# ButterflyFC.net
KiCad netlist of a schematic drawn in EAGLE
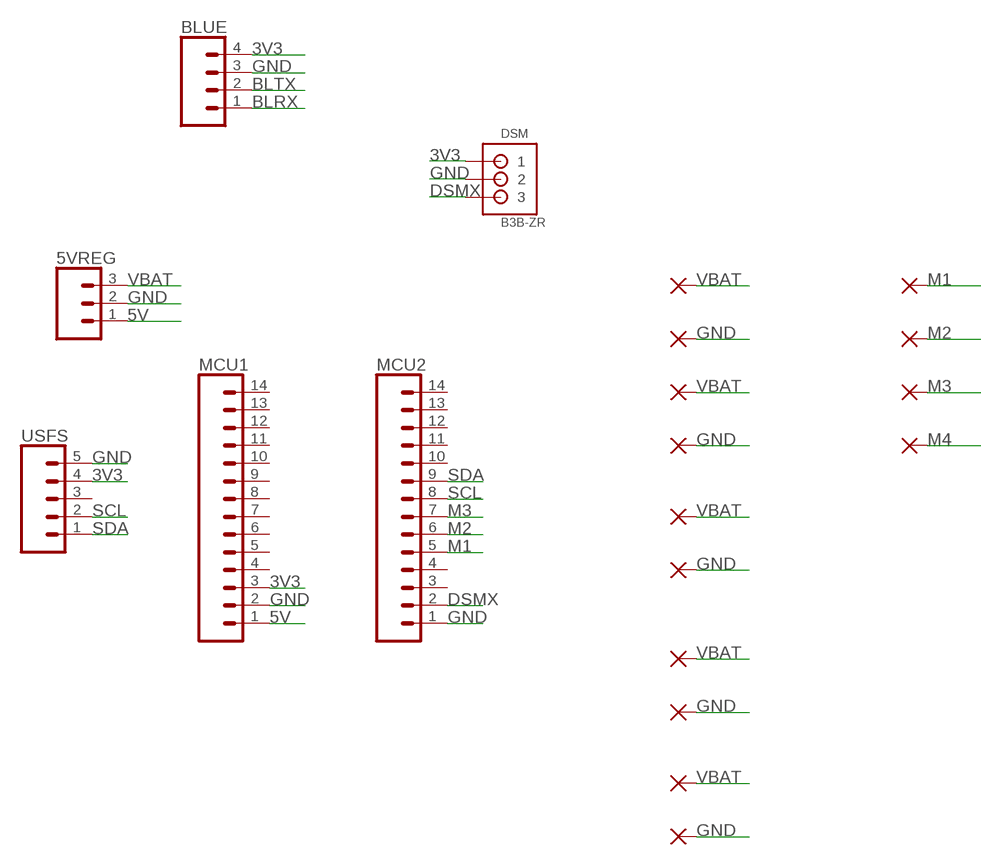
[diagram p0: schematic, sheet 1]

(export (version "E")
  (design (tool "Eeschema 10.0.6"))
  (components
    (comp (ref "5VREG")
      (value "CONN_031X03_NO_SILK")
      (footprint "eagle-import:1X03_NO_SILK")
      (libsource (lib "eagle-import") (part "CONN_031X03_NO_SILK"))
    )
    (comp (ref "BLUE")
      (value "CONN_041X04_NO_SILK")
      (footprint "eagle-import:1X04_NO_SILK")
      (libsource (lib "eagle-import") (part "CONN_041X04_NO_SILK"))
    )
    (comp (ref "DSM")
      (value "B3B-ZR")
      (footprint "eagle-import:B3B-ZR")
      (libsource (lib "eagle-import") (part "B3B-ZR"))
    )
    (comp (ref "MCU1")
      (value "CONN_14NO_SILK")
      (footprint "eagle-import:1X14_NO_SILK")
      (libsource (lib "eagle-import") (part "CONN_14NO_SILK"))
    )
    (comp (ref "MCU2")
      (value "CONN_14NO_SILK")
      (footprint "eagle-import:1X14_NO_SILK")
      (libsource (lib "eagle-import") (part "CONN_14NO_SILK"))
    )
    (comp (ref "PAD1")
      (value "WIREPADSMD5-2,5")
      (footprint "eagle-import:5-2,5")
      (libsource (lib "eagle-import") (part "WIREPADSMD5-2,5"))
    )
    (comp (ref "PAD2")
      (value "WIREPADSMD5-2,5")
      (footprint "eagle-import:5-2,5")
      (libsource (lib "eagle-import") (part "WIREPADSMD5-2,5"))
    )
    (comp (ref "PAD3")
      (value "WIREPADSMD5-2,5")
      (footprint "eagle-import:5-2,5")
      (libsource (lib "eagle-import") (part "WIREPADSMD5-2,5"))
    )
    (comp (ref "PAD4")
      (value "WIREPADSMD5-2,5")
      (footprint "eagle-import:5-2,5")
      (libsource (lib "eagle-import") (part "WIREPADSMD5-2,5"))
    )
    (comp (ref "PAD5")
      (value "WIREPADSMD5-2,5")
      (footprint "eagle-import:5-2,5")
      (libsource (lib "eagle-import") (part "WIREPADSMD5-2,5"))
    )
    (comp (ref "PAD6")
      (value "WIREPADSMD5-2,5")
      (footprint "eagle-import:5-2,5")
      (libsource (lib "eagle-import") (part "WIREPADSMD5-2,5"))
    )
    (comp (ref "PAD7")
      (value "WIREPADSMD5-2,5")
      (footprint "eagle-import:5-2,5")
      (libsource (lib "eagle-import") (part "WIREPADSMD5-2,5"))
    )
    (comp (ref "PAD8")
      (value "WIREPADSMD5-2,5")
      (footprint "eagle-import:5-2,5")
      (libsource (lib "eagle-import") (part "WIREPADSMD5-2,5"))
    )
    (comp (ref "PAD9")
      (value "WIREPADSMD5-2,5")
      (footprint "eagle-import:5-2,5")
      (libsource (lib "eagle-import") (part "WIREPADSMD5-2,5"))
    )
    (comp (ref "PAD10")
      (value "WIREPADSMD5-2,5")
      (footprint "eagle-import:5-2,5")
      (libsource (lib "eagle-import") (part "WIREPADSMD5-2,5"))
    )
    (comp (ref "PAD11")
      (value "WIREPADSMD5-2,5")
      (footprint "eagle-import:5-2,5")
      (libsource (lib "eagle-import") (part "WIREPADSMD5-2,5"))
    )
    (comp (ref "PAD12")
      (value "WIREPADSMD5-2,5")
      (footprint "eagle-import:5-2,5")
      (libsource (lib "eagle-import") (part "WIREPADSMD5-2,5"))
    )
    (comp (ref "PAD13")
      (value "WIREPADSMD5-2,5")
      (footprint "eagle-import:5-2,5")
      (libsource (lib "eagle-import") (part "WIREPADSMD5-2,5"))
    )
    (comp (ref "PAD14")
      (value "WIREPADSMD5-2,5")
      (footprint "eagle-import:5-2,5")
      (libsource (lib "eagle-import") (part "WIREPADSMD5-2,5"))
    )
    (comp (ref "USFS")
      (value "CONN_05NO_SILK")
      (footprint "eagle-import:1X05_NO_SILK")
      (libsource (lib "eagle-import") (part "CONN_05NO_SILK"))
    )
  )
  (nets
    (net (code "1") (name "/3V3") (class "Default")
      (node (ref "BLUE") (pin "4") (pinfunction "4_4") (pintype "passive"))
      (node (ref "DSM") (pin "1") (pinfunction "1_1") (pintype "bidirectional"))
      (node (ref "MCU1") (pin "3") (pinfunction "3_3") (pintype "passive"))
      (node (ref "USFS") (pin "4") (pinfunction "4_4") (pintype "passive"))
    )
    (net (code "2") (name "/5V") (class "Default")
      (node (ref "5VREG") (pin "1") (pinfunction "1_1") (pintype "passive"))
      (node (ref "MCU1") (pin "1") (pinfunction "1_1") (pintype "passive"))
    )
    (net (code "3") (name "/BLRX") (class "Default")
      (node (ref "BLUE") (pin "1") (pinfunction "1_1") (pintype "passive"))
    )
    (net (code "4") (name "/BLTX") (class "Default")
      (node (ref "BLUE") (pin "2") (pinfunction "2_2") (pintype "passive"))
    )
    (net (code "5") (name "/DSMX") (class "Default")
      (node (ref "DSM") (pin "3") (pinfunction "3_3") (pintype "bidirectional"))
      (node (ref "MCU2") (pin "2") (pinfunction "2_2") (pintype "passive"))
    )
    (net (code "6") (name "/GND") (class "Default")
      (node (ref "5VREG") (pin "2") (pinfunction "2_2") (pintype "passive"))
      (node (ref "BLUE") (pin "3") (pinfunction "3_3") (pintype "passive"))
      (node (ref "DSM") (pin "2") (pinfunction "2_2") (pintype "bidirectional"))
      (node (ref "MCU1") (pin "2") (pinfunction "2_2") (pintype "passive"))
      (node (ref "MCU2") (pin "1") (pinfunction "1_1") (pintype "passive"))
      (node (ref "PAD10") (pin "1") (pinfunction "P_1") (pintype "passive"))
      (node (ref "PAD2") (pin "1") (pinfunction "P_1") (pintype "passive"))
      (node (ref "PAD4") (pin "1") (pinfunction "P_1") (pintype "passive"))
      (node (ref "PAD6") (pin "1") (pinfunction "P_1") (pintype "passive"))
      (node (ref "PAD8") (pin "1") (pinfunction "P_1") (pintype "passive"))
      (node (ref "USFS") (pin "5") (pinfunction "5_5") (pintype "passive"))
    )
    (net (code "7") (name "/M1") (class "Default")
      (node (ref "MCU2") (pin "5") (pinfunction "5_5") (pintype "passive"))
      (node (ref "PAD13") (pin "1") (pinfunction "P_1") (pintype "passive"))
    )
    (net (code "8") (name "/M2") (class "Default")
      (node (ref "MCU2") (pin "6") (pinfunction "6_6") (pintype "passive"))
      (node (ref "PAD14") (pin "1") (pinfunction "P_1") (pintype "passive"))
    )
    (net (code "9") (name "/M3") (class "Default")
      (node (ref "MCU2") (pin "7") (pinfunction "7_7") (pintype "passive"))
      (node (ref "PAD11") (pin "1") (pinfunction "P_1") (pintype "passive"))
    )
    (net (code "10") (name "/M4") (class "Default")
      (node (ref "PAD12") (pin "1") (pinfunction "P_1") (pintype "passive"))
    )
    (net (code "11") (name "/SCL") (class "Default")
      (node (ref "MCU2") (pin "8") (pinfunction "8_8") (pintype "passive"))
      (node (ref "USFS") (pin "2") (pinfunction "2_2") (pintype "passive"))
    )
    (net (code "12") (name "/SDA") (class "Default")
      (node (ref "MCU2") (pin "9") (pinfunction "9_9") (pintype "passive"))
      (node (ref "USFS") (pin "1") (pinfunction "1_1") (pintype "passive"))
    )
    (net (code "13") (name "/VBAT") (class "Default")
      (node (ref "5VREG") (pin "3") (pinfunction "3_3") (pintype "passive"))
      (node (ref "PAD1") (pin "1") (pinfunction "P_1") (pintype "passive"))
      (node (ref "PAD3") (pin "1") (pinfunction "P_1") (pintype "passive"))
      (node (ref "PAD5") (pin "1") (pinfunction "P_1") (pintype "passive"))
      (node (ref "PAD7") (pin "1") (pinfunction "P_1") (pintype "passive"))
      (node (ref "PAD9") (pin "1") (pinfunction "P_1") (pintype "passive"))
    )
    (net (code "14") (name "unconnected-(MCU1-Pad4)") (class "Default")
      (node (ref "MCU1") (pin "4") (pinfunction "4_4") (pintype "passive"))
    )
    (net (code "15") (name "unconnected-(MCU1-Pad5)") (class "Default")
      (node (ref "MCU1") (pin "5") (pinfunction "5_5") (pintype "passive"))
    )
    (net (code "16") (name "unconnected-(MCU1-Pad6)") (class "Default")
      (node (ref "MCU1") (pin "6") (pinfunction "6_6") (pintype "passive"))
    )
    (net (code "17") (name "unconnected-(MCU1-Pad7)") (class "Default")
      (node (ref "MCU1") (pin "7") (pinfunction "7_7") (pintype "passive"))
    )
    (net (code "18") (name "unconnected-(MCU1-Pad8)") (class "Default")
      (node (ref "MCU1") (pin "8") (pinfunction "8_8") (pintype "passive"))
    )
    (net (code "19") (name "unconnected-(MCU1-Pad9)") (class "Default")
      (node (ref "MCU1") (pin "9") (pinfunction "9_9") (pintype "passive"))
    )
    (net (code "20") (name "unconnected-(MCU1-Pad10)") (class "Default")
      (node (ref "MCU1") (pin "10") (pinfunction "10_10") (pintype "passive"))
    )
    (net (code "21") (name "unconnected-(MCU1-Pad11)") (class "Default")
      (node (ref "MCU1") (pin "11") (pinfunction "11_11") (pintype "passive"))
    )
    (net (code "22") (name "unconnected-(MCU1-Pad12)") (class "Default")
      (node (ref "MCU1") (pin "12") (pinfunction "12_12") (pintype "passive"))
    )
    (net (code "23") (name "unconnected-(MCU1-Pad13)") (class "Default")
      (node (ref "MCU1") (pin "13") (pinfunction "13_13") (pintype "passive"))
    )
    (net (code "24") (name "unconnected-(MCU1-Pad14)") (class "Default")
      (node (ref "MCU1") (pin "14") (pinfunction "14_14") (pintype "passive"))
    )
    (net (code "25") (name "unconnected-(MCU2-Pad3)") (class "Default")
      (node (ref "MCU2") (pin "3") (pinfunction "3_3") (pintype "passive"))
    )
    (net (code "26") (name "unconnected-(MCU2-Pad4)") (class "Default")
      (node (ref "MCU2") (pin "4") (pinfunction "4_4") (pintype "passive"))
    )
    (net (code "27") (name "unconnected-(MCU2-Pad10)") (class "Default")
      (node (ref "MCU2") (pin "10") (pinfunction "10_10") (pintype "passive"))
    )
    (net (code "28") (name "unconnected-(MCU2-Pad11)") (class "Default")
      (node (ref "MCU2") (pin "11") (pinfunction "11_11") (pintype "passive"))
    )
    (net (code "29") (name "unconnected-(MCU2-Pad12)") (class "Default")
      (node (ref "MCU2") (pin "12") (pinfunction "12_12") (pintype "passive"))
    )
    (net (code "30") (name "unconnected-(MCU2-Pad13)") (class "Default")
      (node (ref "MCU2") (pin "13") (pinfunction "13_13") (pintype "passive"))
    )
    (net (code "31") (name "unconnected-(MCU2-Pad14)") (class "Default")
      (node (ref "MCU2") (pin "14") (pinfunction "14_14") (pintype "passive"))
    )
    (net (code "32") (name "unconnected-(USFS-Pad3)") (class "Default")
      (node (ref "USFS") (pin "3") (pinfunction "3_3") (pintype "passive"))
    )
  )
)
